# 1541-parallel.net
KiCad netlist of a schematic drawn in EAGLE
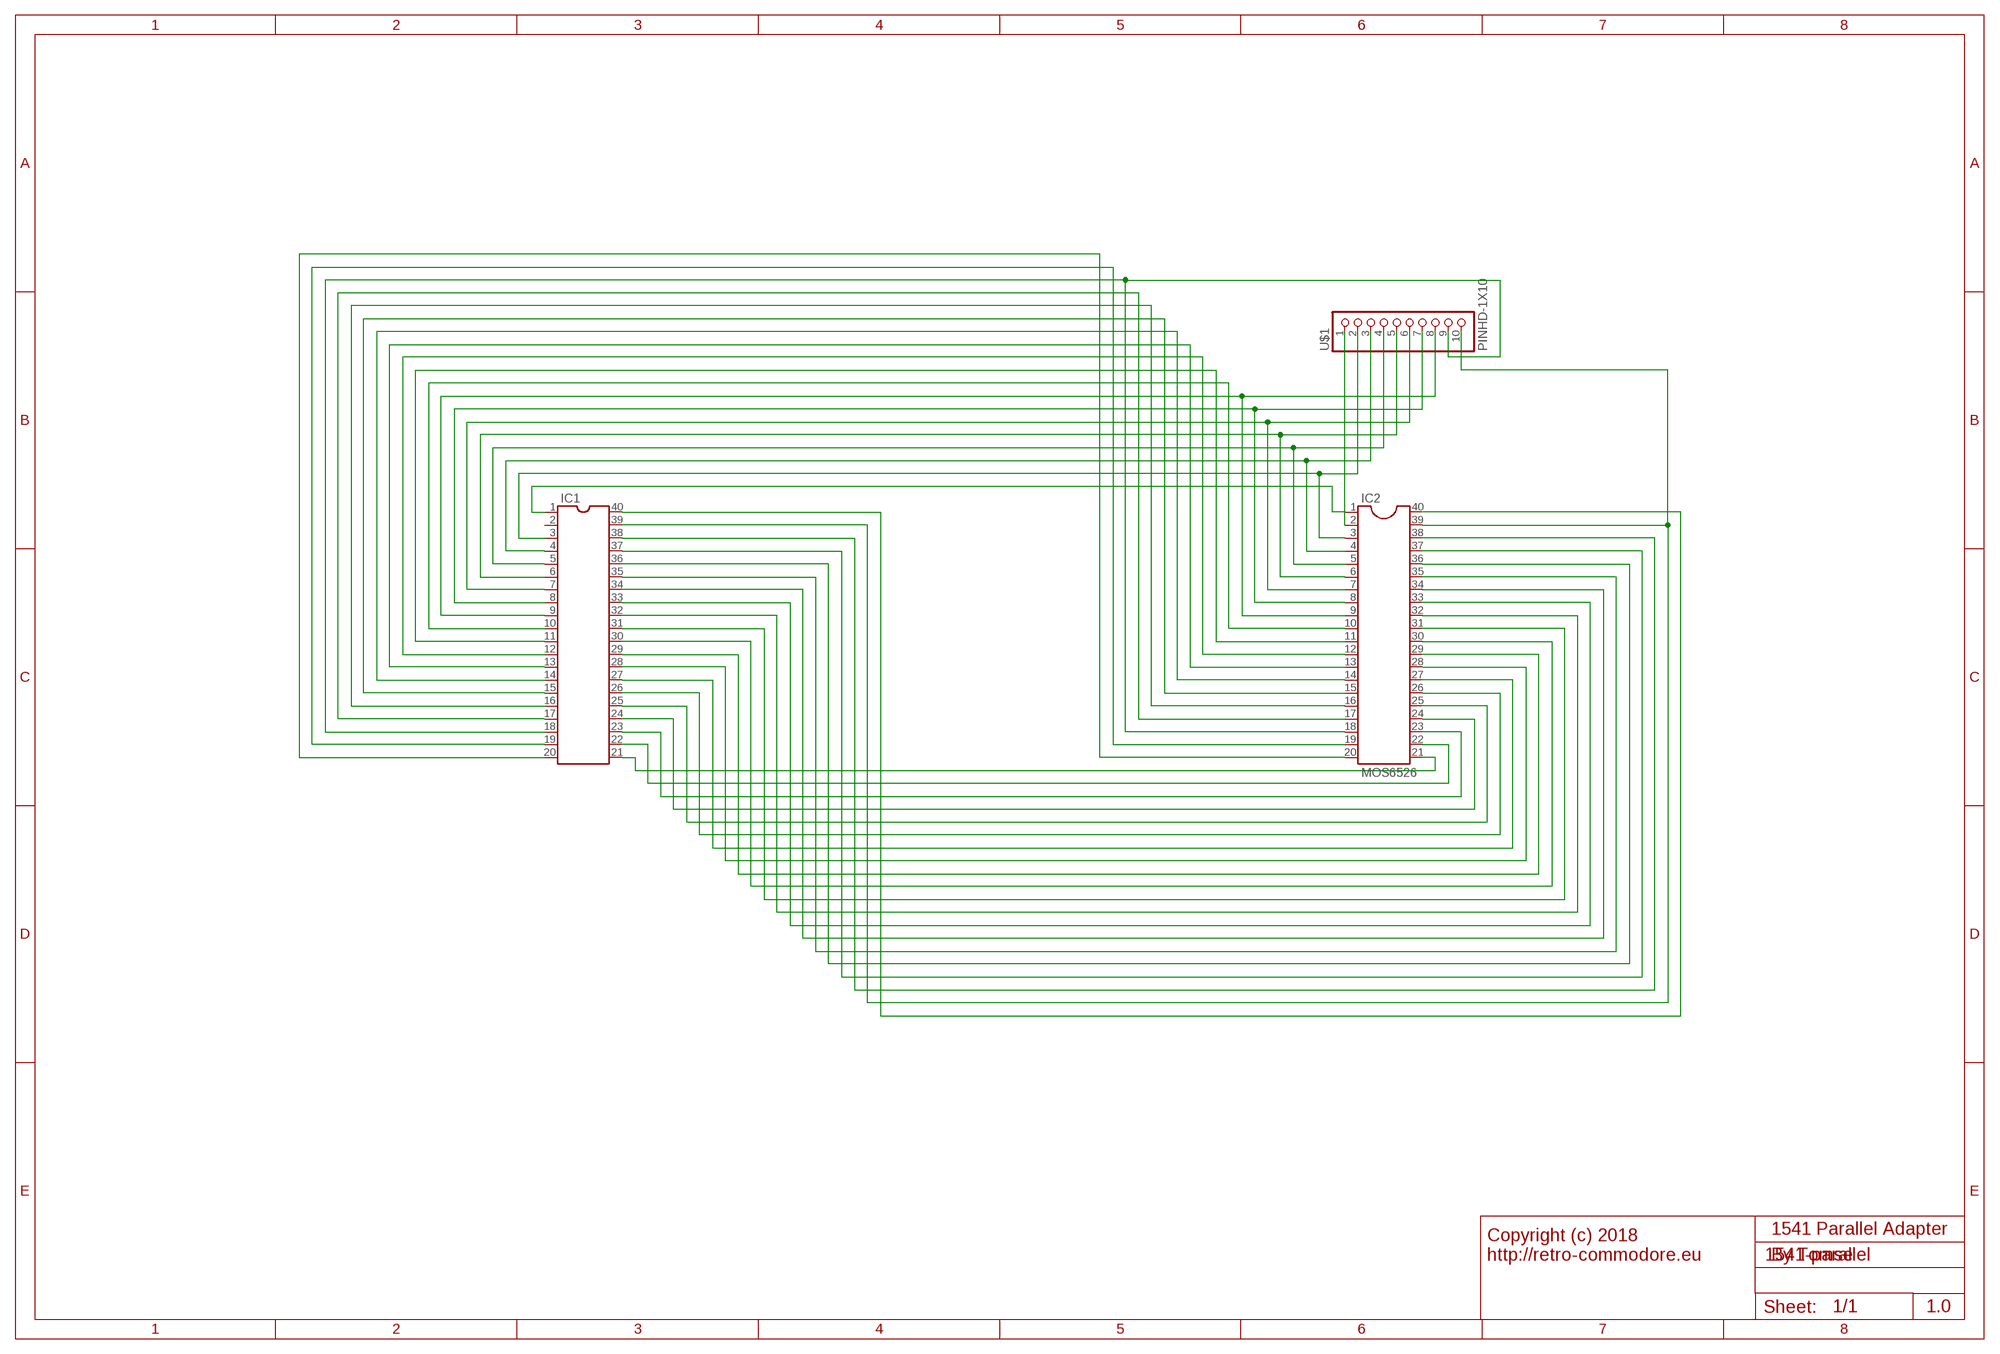
[diagram p0: schematic, sheet 1]

(export (version "E")
  (design (tool "Eeschema 10.0.6"))
  (components
    (comp (ref "IC1")
      (value "IC-PACKAGE_DIL40")
      (footprint "eagle-import:IC-PACKAGE_DIL40")
      (libsource (lib "eagle-import") (part "IC-PACKAGE_DIL40"))
    )
    (comp (ref "IC2")
      (value "MOS6526")
      (footprint "eagle-import:DIL40")
      (fields (field (name "SPICEPREFIX") "X"))
      (libsource (lib "eagle-import") (part "DIL40"))
    )
    (comp (ref "U$1")
      (value "PINHD-1X10")
      (footprint "eagle-import:1X10-BIG")
      (libsource (lib "eagle-import") (part "PINHD-1X10"))
    )
  )
  (nets
    (net (code "1") (name "Net-(IC1-Pad1)") (class "Default")
      (node (ref "IC1") (pin "1") (pinfunction "1_1") (pintype "passive"))
      (node (ref "IC2") (pin "1") (pinfunction "1_1") (pintype "passive"))
    )
    (net (code "2") (name "Net-(IC1-Pad3)") (class "Default")
      (node (ref "IC1") (pin "3") (pinfunction "3_3") (pintype "passive"))
      (node (ref "IC2") (pin "3") (pinfunction "3_3") (pintype "passive"))
      (node (ref "U$1") (pin "2") (pinfunction "2_2") (pintype "passive"))
    )
    (net (code "3") (name "Net-(IC1-Pad4)") (class "Default")
      (node (ref "IC1") (pin "4") (pinfunction "4_4") (pintype "passive"))
      (node (ref "IC2") (pin "4") (pinfunction "4_4") (pintype "passive"))
      (node (ref "U$1") (pin "3") (pinfunction "3_3") (pintype "passive"))
    )
    (net (code "4") (name "Net-(IC1-Pad5)") (class "Default")
      (node (ref "IC1") (pin "5") (pinfunction "5_5") (pintype "passive"))
      (node (ref "IC2") (pin "5") (pinfunction "5_5") (pintype "passive"))
      (node (ref "U$1") (pin "4") (pinfunction "4_4") (pintype "passive"))
    )
    (net (code "5") (name "Net-(IC1-Pad6)") (class "Default")
      (node (ref "IC1") (pin "6") (pinfunction "6_6") (pintype "passive"))
      (node (ref "IC2") (pin "6") (pinfunction "6_6") (pintype "passive"))
      (node (ref "U$1") (pin "5") (pinfunction "5_5") (pintype "passive"))
    )
    (net (code "6") (name "Net-(IC1-Pad7)") (class "Default")
      (node (ref "IC1") (pin "7") (pinfunction "7_7") (pintype "passive"))
      (node (ref "IC2") (pin "7") (pinfunction "7_7") (pintype "passive"))
      (node (ref "U$1") (pin "6") (pinfunction "6_6") (pintype "passive"))
    )
    (net (code "7") (name "Net-(IC1-Pad8)") (class "Default")
      (node (ref "IC1") (pin "8") (pinfunction "8_8") (pintype "passive"))
      (node (ref "IC2") (pin "8") (pinfunction "8_8") (pintype "passive"))
      (node (ref "U$1") (pin "7") (pinfunction "7_7") (pintype "passive"))
    )
    (net (code "8") (name "Net-(IC1-Pad9)") (class "Default")
      (node (ref "IC1") (pin "9") (pinfunction "9_9") (pintype "passive"))
      (node (ref "IC2") (pin "9") (pinfunction "9_9") (pintype "passive"))
      (node (ref "U$1") (pin "8") (pinfunction "8_8") (pintype "passive"))
    )
    (net (code "9") (name "Net-(IC1-Pad10)") (class "Default")
      (node (ref "IC1") (pin "10") (pinfunction "10_10") (pintype "passive"))
      (node (ref "IC2") (pin "10") (pinfunction "10_10") (pintype "passive"))
    )
    (net (code "10") (name "Net-(IC1-Pad11)") (class "Default")
      (node (ref "IC1") (pin "11") (pinfunction "11_11") (pintype "passive"))
      (node (ref "IC2") (pin "11") (pinfunction "11_11") (pintype "passive"))
    )
    (net (code "11") (name "Net-(IC1-Pad12)") (class "Default")
      (node (ref "IC1") (pin "12") (pinfunction "12_12") (pintype "passive"))
      (node (ref "IC2") (pin "12") (pinfunction "12_12") (pintype "passive"))
    )
    (net (code "12") (name "Net-(IC1-Pad13)") (class "Default")
      (node (ref "IC1") (pin "13") (pinfunction "13_13") (pintype "passive"))
      (node (ref "IC2") (pin "13") (pinfunction "13_13") (pintype "passive"))
    )
    (net (code "13") (name "Net-(IC1-Pad14)") (class "Default")
      (node (ref "IC1") (pin "14") (pinfunction "14_14") (pintype "passive"))
      (node (ref "IC2") (pin "14") (pinfunction "14_14") (pintype "passive"))
    )
    (net (code "14") (name "Net-(IC1-Pad15)") (class "Default")
      (node (ref "IC1") (pin "15") (pinfunction "15_15") (pintype "passive"))
      (node (ref "IC2") (pin "15") (pinfunction "15_15") (pintype "passive"))
    )
    (net (code "15") (name "Net-(IC1-Pad16)") (class "Default")
      (node (ref "IC1") (pin "16") (pinfunction "16_16") (pintype "passive"))
      (node (ref "IC2") (pin "16") (pinfunction "16_16") (pintype "passive"))
    )
    (net (code "16") (name "Net-(IC1-Pad17)") (class "Default")
      (node (ref "IC1") (pin "17") (pinfunction "17_17") (pintype "passive"))
      (node (ref "IC2") (pin "17") (pinfunction "17_17") (pintype "passive"))
    )
    (net (code "17") (name "Net-(IC1-Pad18)") (class "Default")
      (node (ref "IC1") (pin "18") (pinfunction "18_18") (pintype "passive"))
      (node (ref "IC2") (pin "18") (pinfunction "18_18") (pintype "passive"))
      (node (ref "U$1") (pin "9") (pinfunction "9_9") (pintype "passive"))
    )
    (net (code "18") (name "Net-(IC1-Pad19)") (class "Default")
      (node (ref "IC1") (pin "19") (pinfunction "19_19") (pintype "passive"))
      (node (ref "IC2") (pin "19") (pinfunction "19_19") (pintype "passive"))
    )
    (net (code "19") (name "Net-(IC1-Pad20)") (class "Default")
      (node (ref "IC1") (pin "20") (pinfunction "20_20") (pintype "passive"))
      (node (ref "IC2") (pin "20") (pinfunction "20_20") (pintype "passive"))
    )
    (net (code "20") (name "Net-(IC1-Pad21)") (class "Default")
      (node (ref "IC1") (pin "21") (pinfunction "21_21") (pintype "passive"))
      (node (ref "IC2") (pin "21") (pinfunction "21_21") (pintype "passive"))
    )
    (net (code "21") (name "Net-(IC1-Pad22)") (class "Default")
      (node (ref "IC1") (pin "22") (pinfunction "22_22") (pintype "passive"))
      (node (ref "IC2") (pin "22") (pinfunction "22_22") (pintype "passive"))
    )
    (net (code "22") (name "Net-(IC1-Pad23)") (class "Default")
      (node (ref "IC1") (pin "23") (pinfunction "23_23") (pintype "passive"))
      (node (ref "IC2") (pin "23") (pinfunction "23_23") (pintype "passive"))
    )
    (net (code "23") (name "Net-(IC1-Pad24)") (class "Default")
      (node (ref "IC1") (pin "24") (pinfunction "24_24") (pintype "passive"))
      (node (ref "IC2") (pin "24") (pinfunction "24_24") (pintype "passive"))
    )
    (net (code "24") (name "Net-(IC1-Pad25)") (class "Default")
      (node (ref "IC1") (pin "25") (pinfunction "25_25") (pintype "passive"))
      (node (ref "IC2") (pin "25") (pinfunction "25_25") (pintype "passive"))
    )
    (net (code "25") (name "Net-(IC1-Pad26)") (class "Default")
      (node (ref "IC1") (pin "26") (pinfunction "26_26") (pintype "passive"))
      (node (ref "IC2") (pin "26") (pinfunction "26_26") (pintype "passive"))
    )
    (net (code "26") (name "Net-(IC1-Pad27)") (class "Default")
      (node (ref "IC1") (pin "27") (pinfunction "27_27") (pintype "passive"))
      (node (ref "IC2") (pin "27") (pinfunction "27_27") (pintype "passive"))
    )
    (net (code "27") (name "Net-(IC1-Pad28)") (class "Default")
      (node (ref "IC1") (pin "28") (pinfunction "28_28") (pintype "passive"))
      (node (ref "IC2") (pin "28") (pinfunction "28_28") (pintype "passive"))
    )
    (net (code "28") (name "Net-(IC1-Pad29)") (class "Default")
      (node (ref "IC1") (pin "29") (pinfunction "29_29") (pintype "passive"))
      (node (ref "IC2") (pin "29") (pinfunction "29_29") (pintype "passive"))
    )
    (net (code "29") (name "Net-(IC1-Pad30)") (class "Default")
      (node (ref "IC1") (pin "30") (pinfunction "30_30") (pintype "passive"))
      (node (ref "IC2") (pin "30") (pinfunction "30_30") (pintype "passive"))
    )
    (net (code "30") (name "Net-(IC1-Pad31)") (class "Default")
      (node (ref "IC1") (pin "31") (pinfunction "31_31") (pintype "passive"))
      (node (ref "IC2") (pin "31") (pinfunction "31_31") (pintype "passive"))
    )
    (net (code "31") (name "Net-(IC1-Pad32)") (class "Default")
      (node (ref "IC1") (pin "32") (pinfunction "32_32") (pintype "passive"))
      (node (ref "IC2") (pin "32") (pinfunction "32_32") (pintype "passive"))
    )
    (net (code "32") (name "Net-(IC1-Pad33)") (class "Default")
      (node (ref "IC1") (pin "33") (pinfunction "33_33") (pintype "passive"))
      (node (ref "IC2") (pin "33") (pinfunction "33_33") (pintype "passive"))
    )
    (net (code "33") (name "Net-(IC1-Pad34)") (class "Default")
      (node (ref "IC1") (pin "34") (pinfunction "34_34") (pintype "passive"))
      (node (ref "IC2") (pin "34") (pinfunction "34_34") (pintype "passive"))
    )
    (net (code "34") (name "Net-(IC1-Pad35)") (class "Default")
      (node (ref "IC1") (pin "35") (pinfunction "35_35") (pintype "passive"))
      (node (ref "IC2") (pin "35") (pinfunction "35_35") (pintype "passive"))
    )
    (net (code "35") (name "Net-(IC1-Pad36)") (class "Default")
      (node (ref "IC1") (pin "36") (pinfunction "36_36") (pintype "passive"))
      (node (ref "IC2") (pin "36") (pinfunction "36_36") (pintype "passive"))
    )
    (net (code "36") (name "Net-(IC1-Pad37)") (class "Default")
      (node (ref "IC1") (pin "37") (pinfunction "37_37") (pintype "passive"))
      (node (ref "IC2") (pin "37") (pinfunction "37_37") (pintype "passive"))
    )
    (net (code "37") (name "Net-(IC1-Pad38)") (class "Default")
      (node (ref "IC1") (pin "38") (pinfunction "38_38") (pintype "passive"))
      (node (ref "IC2") (pin "38") (pinfunction "38_38") (pintype "passive"))
    )
    (net (code "38") (name "Net-(IC1-Pad39)") (class "Default")
      (node (ref "IC1") (pin "39") (pinfunction "39_39") (pintype "passive"))
      (node (ref "IC2") (pin "39") (pinfunction "39_39") (pintype "passive"))
      (node (ref "U$1") (pin "10") (pinfunction "10_10") (pintype "passive"))
    )
    (net (code "39") (name "Net-(IC1-Pad40)") (class "Default")
      (node (ref "IC1") (pin "40") (pinfunction "40_40") (pintype "passive"))
      (node (ref "IC2") (pin "40") (pinfunction "40_40") (pintype "passive"))
    )
    (net (code "40") (name "Net-(IC2-Pad2)") (class "Default")
      (node (ref "IC2") (pin "2") (pinfunction "2_2") (pintype "passive"))
      (node (ref "U$1") (pin "1") (pinfunction "1_1") (pintype "passive"))
    )
    (net (code "41") (name "unconnected-(IC1-Pad2)") (class "Default")
      (node (ref "IC1") (pin "2") (pinfunction "2_2") (pintype "passive"))
    )
  )
)
